# vectrex_rom_27c1001_1_pcb.net
KiCad netlist of a schematic drawn in EAGLE
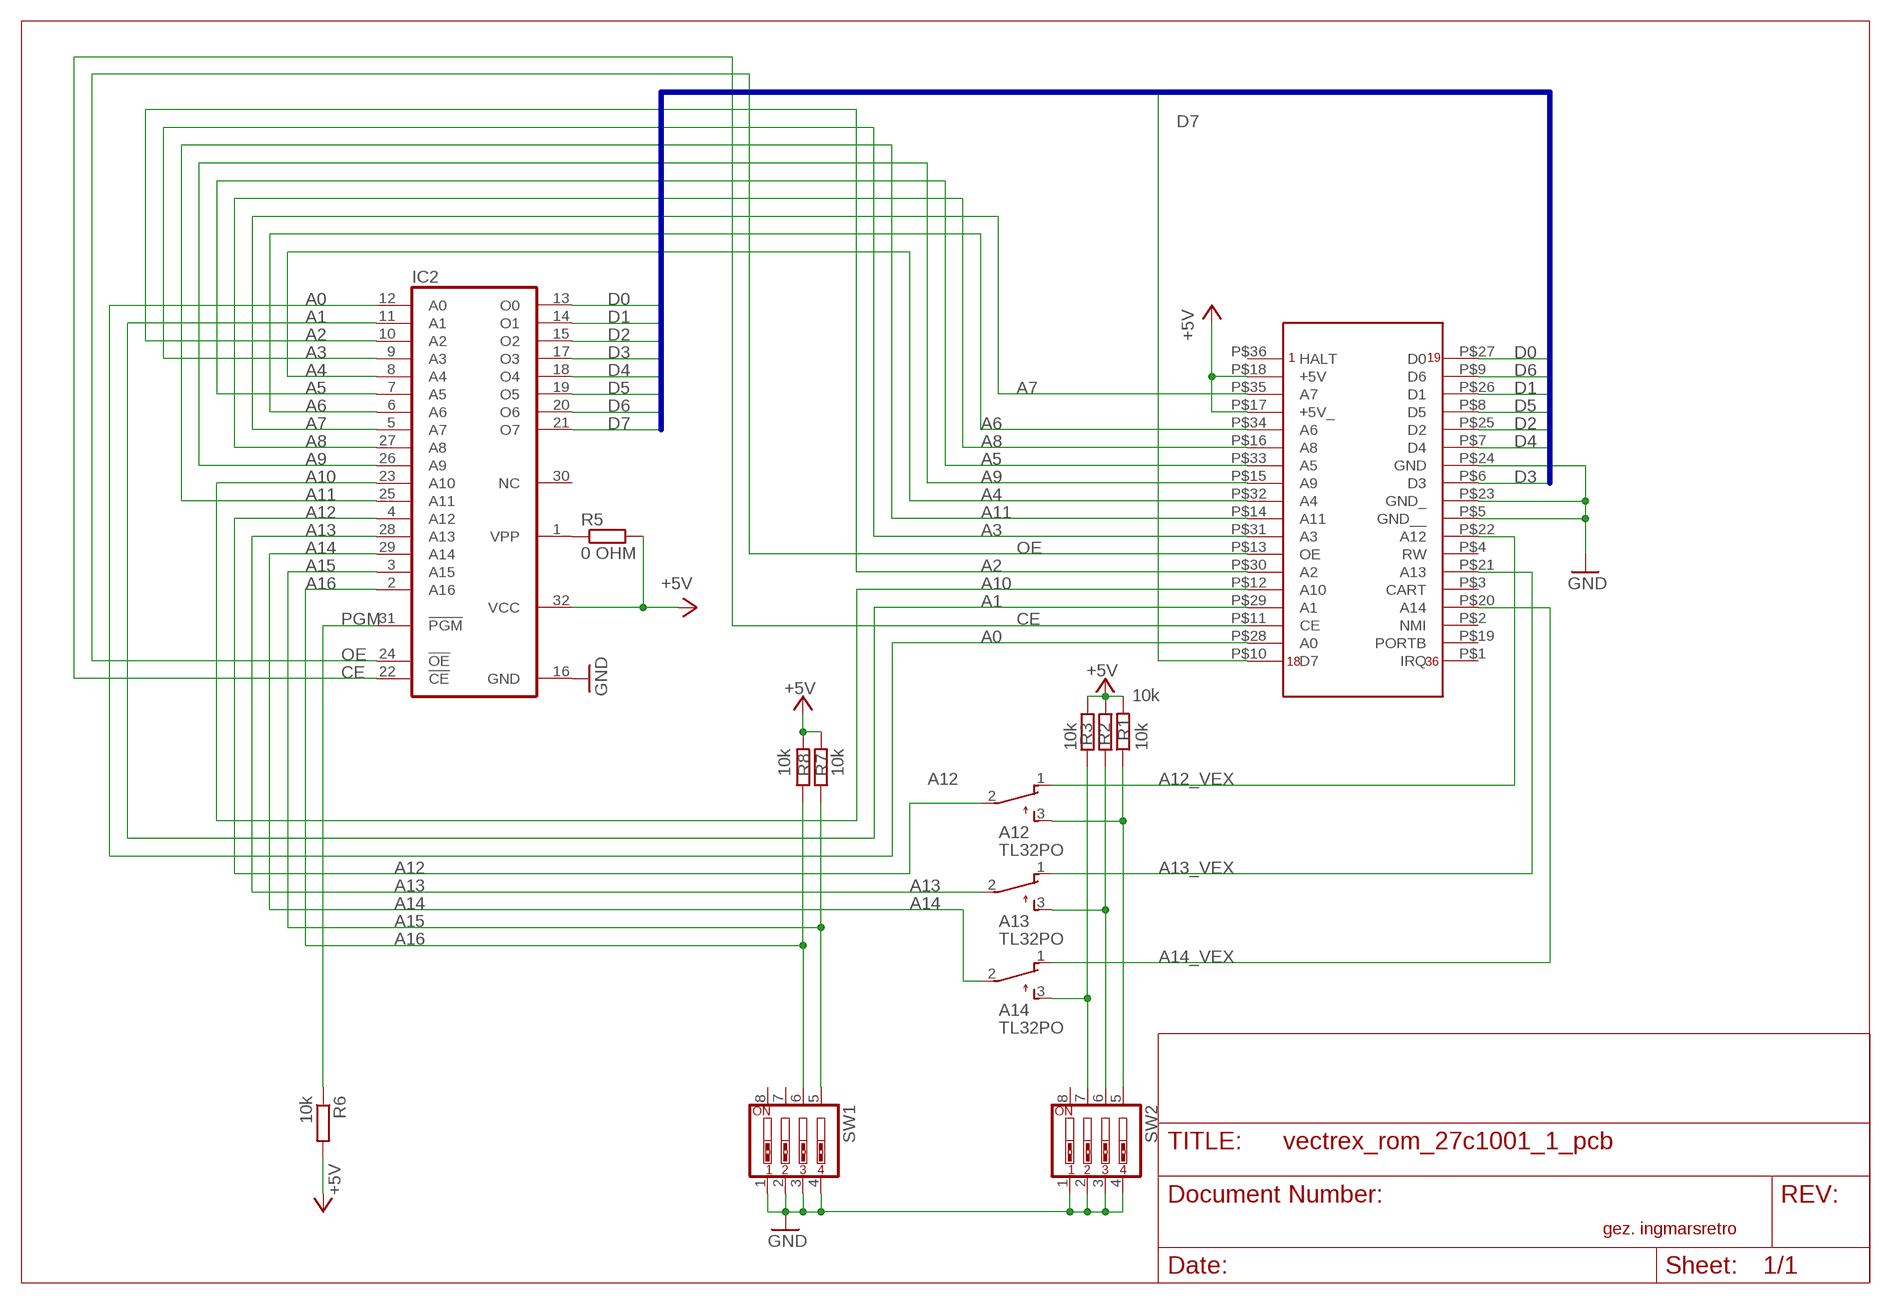
[diagram p0: schematic, sheet 1]

(export (version "E")
  (design (tool "Eeschema 10.0.6"))
  (components
    (comp (ref "A12")
      (value "TL32PO")
      (footprint "eagle-import:TL3XPO")
      (libsource (lib "eagle-import") (part "TL32PO"))
    )
    (comp (ref "A13")
      (value "TL32PO")
      (footprint "eagle-import:TL3XPO")
      (libsource (lib "eagle-import") (part "TL32PO"))
    )
    (comp (ref "A14")
      (value "TL32PO")
      (footprint "eagle-import:TL3XPO")
      (libsource (lib "eagle-import") (part "TL32PO"))
    )
    (comp (ref "IC2")
      (value "27C1001A")
      (footprint "eagle-import:DIL32")
      (fields (field (name "MPN") "M27C1001-15F1"))
      (libsource (lib "eagle-import") (part "27C1001A"))
    )
    (comp (ref "R1")
      (value "10k")
      (footprint "eagle-import:R0805")
      (libsource (lib "eagle-import") (part "R-EU_R0805"))
    )
    (comp (ref "R2")
      (value "10k")
      (footprint "eagle-import:R0805")
      (libsource (lib "eagle-import") (part "R-EU_R0805"))
    )
    (comp (ref "R3")
      (value "10k")
      (footprint "eagle-import:R0805")
      (libsource (lib "eagle-import") (part "R-EU_R0805"))
    )
    (comp (ref "R5")
      (value "0 OHM")
      (footprint "eagle-import:R0805")
      (libsource (lib "eagle-import") (part "R-EU_R0805"))
    )
    (comp (ref "R6")
      (value "10k")
      (footprint "eagle-import:R0805")
      (libsource (lib "eagle-import") (part "R-EU_R0805"))
    )
    (comp (ref "R7")
      (value "10k")
      (footprint "eagle-import:R0805")
      (libsource (lib "eagle-import") (part "R-EU_R0805"))
    )
    (comp (ref "R8")
      (value "10k")
      (footprint "eagle-import:R0805")
      (libsource (lib "eagle-import") (part "R-EU_R0805"))
    )
    (comp (ref "SW1")
      (value "SW_DIP-4")
      (footprint "eagle-import:EDG-04")
      (libsource (lib "eagle-import") (part "SW_DIP-4"))
    )
    (comp (ref "SW2")
      (value "SW_DIP-4")
      (footprint "eagle-import:EDG-04")
      (libsource (lib "eagle-import") (part "SW_DIP-4"))
    )
    (comp (ref "U$1")
      (value "VECTREX_ROMCONNECTOR")
      (footprint "eagle-import:ROM_CONNECTOR_PCB")
      (libsource (lib "eagle-import") (part "VECTREX_ROMCONNECTOR"))
    )
  )
  (nets
    (net (code "1") (name "+5V") (class "Default")
      (node (ref "IC2") (pin "32") (pinfunction "VCC_32") (pintype "power_in"))
      (node (ref "R1") (pin "2") (pinfunction "2_2") (pintype "passive"))
      (node (ref "R2") (pin "1") (pinfunction "1_1") (pintype "passive"))
      (node (ref "R3") (pin "1") (pinfunction "1_1") (pintype "passive"))
      (node (ref "R5") (pin "2") (pinfunction "2_2") (pintype "passive"))
      (node (ref "R6") (pin "2") (pinfunction "2_2") (pintype "passive"))
      (node (ref "R7") (pin "2") (pinfunction "2_2") (pintype "passive"))
      (node (ref "R8") (pin "2") (pinfunction "2_2") (pintype "passive"))
      (node (ref "U$1") (pin "P$17") (pinfunction "+5V__P$17") (pintype "bidirectional"))
      (node (ref "U$1") (pin "P$18") (pinfunction "+5V_P$18") (pintype "bidirectional"))
    )
    (net (code "2") (name "/A0") (class "Default")
      (node (ref "IC2") (pin "12") (pinfunction "A0_12") (pintype "input"))
      (node (ref "U$1") (pin "P$28") (pinfunction "A0_P$28") (pintype "bidirectional"))
    )
    (net (code "3") (name "/A1") (class "Default")
      (node (ref "IC2") (pin "11") (pinfunction "A1_11") (pintype "input"))
      (node (ref "U$1") (pin "P$29") (pinfunction "A1_P$29") (pintype "bidirectional"))
    )
    (net (code "4") (name "/A2") (class "Default")
      (node (ref "IC2") (pin "10") (pinfunction "A2_10") (pintype "input"))
      (node (ref "U$1") (pin "P$30") (pinfunction "A2_P$30") (pintype "bidirectional"))
    )
    (net (code "5") (name "/A3") (class "Default")
      (node (ref "IC2") (pin "9") (pinfunction "A3_9") (pintype "input"))
      (node (ref "U$1") (pin "P$31") (pinfunction "A3_P$31") (pintype "bidirectional"))
    )
    (net (code "6") (name "/A4") (class "Default")
      (node (ref "IC2") (pin "8") (pinfunction "A4_8") (pintype "input"))
      (node (ref "U$1") (pin "P$32") (pinfunction "A4_P$32") (pintype "bidirectional"))
    )
    (net (code "7") (name "/A5") (class "Default")
      (node (ref "IC2") (pin "7") (pinfunction "A5_7") (pintype "input"))
      (node (ref "U$1") (pin "P$33") (pinfunction "A5_P$33") (pintype "bidirectional"))
    )
    (net (code "8") (name "/A6") (class "Default")
      (node (ref "IC2") (pin "6") (pinfunction "A6_6") (pintype "input"))
      (node (ref "U$1") (pin "P$34") (pinfunction "A6_P$34") (pintype "bidirectional"))
    )
    (net (code "9") (name "/A7") (class "Default")
      (node (ref "IC2") (pin "5") (pinfunction "A7_5") (pintype "input"))
      (node (ref "U$1") (pin "P$35") (pinfunction "A7_P$35") (pintype "bidirectional"))
    )
    (net (code "10") (name "/A8") (class "Default")
      (node (ref "IC2") (pin "27") (pinfunction "A8_27") (pintype "input"))
      (node (ref "U$1") (pin "P$16") (pinfunction "A8_P$16") (pintype "bidirectional"))
    )
    (net (code "11") (name "/A9") (class "Default")
      (node (ref "IC2") (pin "26") (pinfunction "A9_26") (pintype "input"))
      (node (ref "U$1") (pin "P$15") (pinfunction "A9_P$15") (pintype "bidirectional"))
    )
    (net (code "12") (name "/A10") (class "Default")
      (node (ref "IC2") (pin "23") (pinfunction "A10_23") (pintype "input"))
      (node (ref "U$1") (pin "P$12") (pinfunction "A10_P$12") (pintype "bidirectional"))
    )
    (net (code "13") (name "/A11") (class "Default")
      (node (ref "IC2") (pin "25") (pinfunction "A11_25") (pintype "input"))
      (node (ref "U$1") (pin "P$14") (pinfunction "A11_P$14") (pintype "bidirectional"))
    )
    (net (code "14") (name "/A12") (class "Default")
      (node (ref "A12") (pin "2") (pinfunction "P_2") (pintype "passive"))
      (node (ref "IC2") (pin "4") (pinfunction "A12_4") (pintype "input"))
    )
    (net (code "15") (name "/A12_VEX") (class "Default")
      (node (ref "A12") (pin "1") (pinfunction "O_1") (pintype "passive"))
      (node (ref "U$1") (pin "P$22") (pinfunction "A12_P$22") (pintype "bidirectional"))
    )
    (net (code "16") (name "/A13") (class "Default")
      (node (ref "A13") (pin "2") (pinfunction "P_2") (pintype "passive"))
      (node (ref "IC2") (pin "28") (pinfunction "A13_28") (pintype "input"))
    )
    (net (code "17") (name "/A13_VEX") (class "Default")
      (node (ref "A13") (pin "1") (pinfunction "O_1") (pintype "passive"))
      (node (ref "U$1") (pin "P$21") (pinfunction "A13_P$21") (pintype "bidirectional"))
    )
    (net (code "18") (name "/A14") (class "Default")
      (node (ref "A14") (pin "2") (pinfunction "P_2") (pintype "passive"))
      (node (ref "IC2") (pin "29") (pinfunction "A14_29") (pintype "input"))
    )
    (net (code "19") (name "/A14_VEX") (class "Default")
      (node (ref "A14") (pin "1") (pinfunction "O_1") (pintype "passive"))
      (node (ref "U$1") (pin "P$20") (pinfunction "A14_P$20") (pintype "bidirectional"))
    )
    (net (code "20") (name "/A15") (class "Default")
      (node (ref "IC2") (pin "3") (pinfunction "A15_3") (pintype "input"))
      (node (ref "R7") (pin "1") (pinfunction "1_1") (pintype "passive"))
      (node (ref "SW1") (pin "5") (pinfunction "5_5") (pintype "passive"))
    )
    (net (code "21") (name "/A16") (class "Default")
      (node (ref "IC2") (pin "2") (pinfunction "A16_2") (pintype "input"))
      (node (ref "R8") (pin "1") (pinfunction "1_1") (pintype "passive"))
      (node (ref "SW1") (pin "6") (pinfunction "6_6") (pintype "passive"))
    )
    (net (code "22") (name "/CE") (class "Default")
      (node (ref "IC2") (pin "22") (pinfunction "~{CE}_22") (pintype "input"))
      (node (ref "U$1") (pin "P$11") (pinfunction "CE_P$11") (pintype "bidirectional"))
    )
    (net (code "23") (name "/D0") (class "Default")
      (node (ref "IC2") (pin "13") (pinfunction "O0_13") (pintype "tri_state"))
      (node (ref "U$1") (pin "P$27") (pinfunction "D0_P$27") (pintype "bidirectional"))
    )
    (net (code "24") (name "/D1") (class "Default")
      (node (ref "IC2") (pin "14") (pinfunction "O1_14") (pintype "tri_state"))
      (node (ref "U$1") (pin "P$26") (pinfunction "D1_P$26") (pintype "bidirectional"))
    )
    (net (code "25") (name "/D2") (class "Default")
      (node (ref "IC2") (pin "15") (pinfunction "O2_15") (pintype "tri_state"))
      (node (ref "U$1") (pin "P$25") (pinfunction "D2_P$25") (pintype "bidirectional"))
    )
    (net (code "26") (name "/D3") (class "Default")
      (node (ref "IC2") (pin "17") (pinfunction "O3_17") (pintype "tri_state"))
      (node (ref "U$1") (pin "P$6") (pinfunction "D3_P$6") (pintype "bidirectional"))
    )
    (net (code "27") (name "/D4") (class "Default")
      (node (ref "IC2") (pin "18") (pinfunction "O4_18") (pintype "tri_state"))
      (node (ref "U$1") (pin "P$7") (pinfunction "D4_P$7") (pintype "bidirectional"))
    )
    (net (code "28") (name "/D5") (class "Default")
      (node (ref "IC2") (pin "19") (pinfunction "O5_19") (pintype "tri_state"))
      (node (ref "U$1") (pin "P$8") (pinfunction "D5_P$8") (pintype "bidirectional"))
    )
    (net (code "29") (name "/D6") (class "Default")
      (node (ref "IC2") (pin "20") (pinfunction "O6_20") (pintype "tri_state"))
      (node (ref "U$1") (pin "P$9") (pinfunction "D6_P$9") (pintype "bidirectional"))
    )
    (net (code "30") (name "/D7") (class "Default")
      (node (ref "IC2") (pin "21") (pinfunction "O7_21") (pintype "tri_state"))
      (node (ref "U$1") (pin "P$10") (pinfunction "D7_P$10") (pintype "bidirectional"))
    )
    (net (code "31") (name "/OE") (class "Default")
      (node (ref "IC2") (pin "24") (pinfunction "~{OE}_24") (pintype "input"))
      (node (ref "U$1") (pin "P$13") (pinfunction "OE_P$13") (pintype "bidirectional"))
    )
    (net (code "32") (name "/PGM") (class "Default")
      (node (ref "IC2") (pin "31") (pinfunction "~{PGM}_31") (pintype "input"))
      (node (ref "R6") (pin "1") (pinfunction "1_1") (pintype "passive"))
    )
    (net (code "33") (name "GND") (class "Default")
      (node (ref "IC2") (pin "16") (pinfunction "GND_16") (pintype "power_in"))
      (node (ref "SW1") (pin "1") (pinfunction "1_1") (pintype "passive"))
      (node (ref "SW1") (pin "2") (pinfunction "2_2") (pintype "passive"))
      (node (ref "SW1") (pin "3") (pinfunction "3_3") (pintype "passive"))
      (node (ref "SW1") (pin "4") (pinfunction "4_4") (pintype "passive"))
      (node (ref "SW2") (pin "1") (pinfunction "1_1") (pintype "passive"))
      (node (ref "SW2") (pin "2") (pinfunction "2_2") (pintype "passive"))
      (node (ref "SW2") (pin "3") (pinfunction "3_3") (pintype "passive"))
      (node (ref "SW2") (pin "4") (pinfunction "4_4") (pintype "passive"))
      (node (ref "U$1") (pin "P$23") (pinfunction "GND__P$23") (pintype "bidirectional"))
      (node (ref "U$1") (pin "P$24") (pinfunction "GND_P$24") (pintype "bidirectional"))
      (node (ref "U$1") (pin "P$5") (pinfunction "GND___P$5") (pintype "bidirectional"))
    )
    (net (code "34") (name "Net-(A12-S)") (class "Default")
      (node (ref "A12") (pin "3") (pinfunction "S_3") (pintype "passive"))
      (node (ref "R1") (pin "1") (pinfunction "1_1") (pintype "passive"))
      (node (ref "SW2") (pin "5") (pinfunction "5_5") (pintype "passive"))
    )
    (net (code "35") (name "Net-(A13-S)") (class "Default")
      (node (ref "A13") (pin "3") (pinfunction "S_3") (pintype "passive"))
      (node (ref "R2") (pin "2") (pinfunction "2_2") (pintype "passive"))
      (node (ref "SW2") (pin "6") (pinfunction "6_6") (pintype "passive"))
    )
    (net (code "36") (name "Net-(A14-S)") (class "Default")
      (node (ref "A14") (pin "3") (pinfunction "S_3") (pintype "passive"))
      (node (ref "R3") (pin "2") (pinfunction "2_2") (pintype "passive"))
      (node (ref "SW2") (pin "7") (pinfunction "7_7") (pintype "passive"))
    )
    (net (code "37") (name "Net-(IC2-VPP)") (class "Default")
      (node (ref "IC2") (pin "1") (pinfunction "VPP_1") (pintype "passive"))
      (node (ref "R5") (pin "1") (pinfunction "1_1") (pintype "passive"))
    )
    (net (code "38") (name "unconnected-(IC2-NC-Pad30)") (class "Default")
      (node (ref "IC2") (pin "30") (pinfunction "NC_30") (pintype "no_connect"))
    )
    (net (code "39") (name "unconnected-(SW1-Pad7)") (class "Default")
      (node (ref "SW1") (pin "7") (pinfunction "7_7") (pintype "passive"))
    )
    (net (code "40") (name "unconnected-(SW1-Pad8)") (class "Default")
      (node (ref "SW1") (pin "8") (pinfunction "8_8") (pintype "passive"))
    )
    (net (code "41") (name "unconnected-(SW2-Pad8)") (class "Default")
      (node (ref "SW2") (pin "8") (pinfunction "8_8") (pintype "passive"))
    )
    (net (code "42") (name "unconnected-(U$1-CART-PadP$3)") (class "Default")
      (node (ref "U$1") (pin "P$3") (pinfunction "CART_P$3") (pintype "bidirectional"))
    )
    (net (code "43") (name "unconnected-(U$1-HALT-PadP$36)") (class "Default")
      (node (ref "U$1") (pin "P$36") (pinfunction "HALT_P$36") (pintype "bidirectional"))
    )
    (net (code "44") (name "unconnected-(U$1-IRQ-PadP$1)") (class "Default")
      (node (ref "U$1") (pin "P$1") (pinfunction "IRQ_P$1") (pintype "bidirectional"))
    )
    (net (code "45") (name "unconnected-(U$1-NMI-PadP$2)") (class "Default")
      (node (ref "U$1") (pin "P$2") (pinfunction "NMI_P$2") (pintype "bidirectional"))
    )
    (net (code "46") (name "unconnected-(U$1-PORTB-PadP$19)") (class "Default")
      (node (ref "U$1") (pin "P$19") (pinfunction "PORTB_P$19") (pintype "bidirectional"))
    )
    (net (code "47") (name "unconnected-(U$1-RW-PadP$4)") (class "Default")
      (node (ref "U$1") (pin "P$4") (pinfunction "RW_P$4") (pintype "bidirectional"))
    )
  )
)
